# MCU152A_F28E12X_Device.net
KiCad netlist of a schematic drawn in Altium Designer
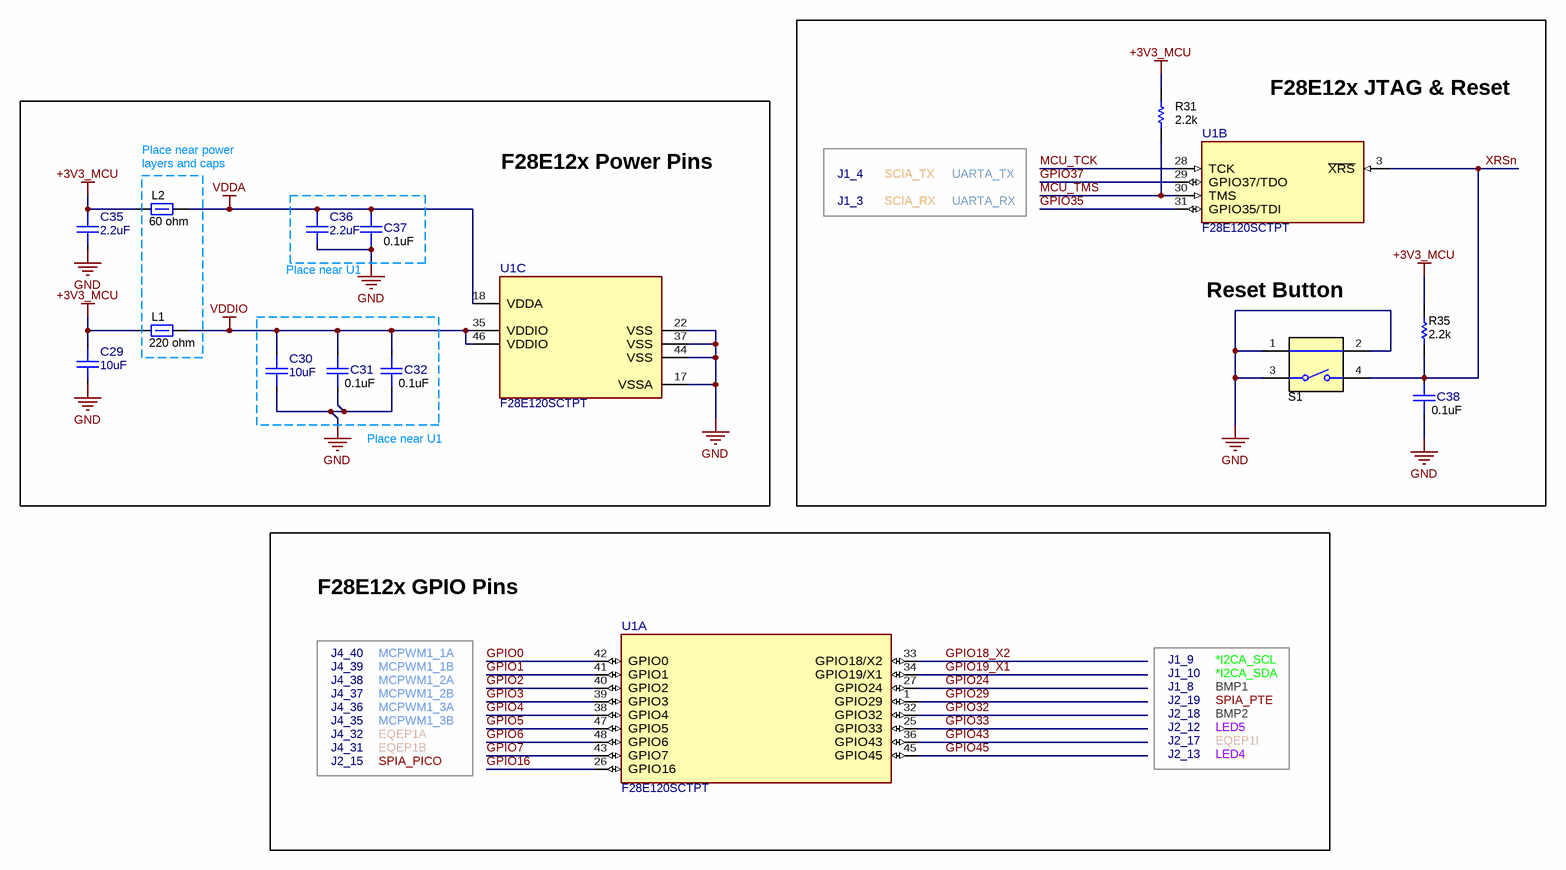
[diagram p0: MCU152A_F28E12X_Device.SchDoc]

(export (version "E")
  (design (tool "Eeschema 10.0.6"))
  (components
    (comp (ref "C29")
      (value "885012106031")
      (footprint "FP-885012106031_0603-MFG")
      (description "10 µF ±20% 25V Ceramic Capacitor X5R 0603 (1608 Metric)")
      (fields (field (name "MANUFACTURER") "Wurth") (field (name "VALUEDISPLAYED") "10uF"))
      (libsource (lib "Altium Vault - TI") (part "SYM-885012106031"))
    )
    (comp (ref "C30")
      (value "885012106031")
      (footprint "FP-885012106031_0603-MFG")
      (description "10 µF ±20% 25V Ceramic Capacitor X5R 0603 (1608 Metric)")
      (fields (field (name "MANUFACTURER") "Wurth") (field (name "VALUEDISPLAYED") "10uF"))
      (libsource (lib "Altium Vault - TI") (part "SYM-885012106031"))
    )
    (comp (ref "C31")
      (value "885012205018")
      (footprint "FP-885012205018_0402-MFG")
      (description "0.1µF ±10% 10V Ceramic Capacitor X7R 0402 (1005 Metric)")
      (fields
        (field (name "MANUFACTURER") "Wurth Electronics")
        (field (name "MOUSER PART NUMBER") "710-885012205018")
        (field (name "VALUEDISPLAYED") "0.1uF")
      )
      (libsource (lib "Altium Vault - TI") (part "SYM-885012205018"))
    )
    (comp (ref "C32")
      (value "885012205018")
      (footprint "FP-885012205018_0402-MFG")
      (description "0.1µF ±10% 10V Ceramic Capacitor X7R 0402 (1005 Metric)")
      (fields
        (field (name "MANUFACTURER") "Wurth Electronics")
        (field (name "MOUSER PART NUMBER") "710-885012205018")
        (field (name "VALUEDISPLAYED") "0.1uF")
      )
      (libsource (lib "Altium Vault - TI") (part "SYM-885012205018"))
    )
    (comp (ref "C35")
      (value "885012106011")
      (footprint "FP-885012106011_0603-MFG")
      (description "2.2 µF ±20% 10V Ceramic Capacitor X5R 0603 (1608 Metric)")
      (fields
        (field (name "MANUFACTURER") "Wurth Electronics")
        (field (name "VALUEDISPLAYED") "2.2uF")
        (field (name "DIGIKEY PART NUMBER") "732-7908-1-ND")
      )
      (libsource (lib "Altium Vault - TI") (part "SYM-885012106011"))
    )
    (comp (ref "C36")
      (value "885012106011")
      (footprint "FP-885012106011_0603-MFG")
      (description "2.2 µF ±20% 10V Ceramic Capacitor X5R 0603 (1608 Metric)")
      (fields
        (field (name "MANUFACTURER") "Wurth Electronics")
        (field (name "VALUEDISPLAYED") "2.2uF")
        (field (name "DIGIKEY PART NUMBER") "732-7908-1-ND")
      )
      (libsource (lib "Altium Vault - TI") (part "SYM-885012106011"))
    )
    (comp (ref "C37")
      (value "885012205018")
      (footprint "FP-885012205018_0402-MFG")
      (description "0.1µF ±10% 10V Ceramic Capacitor X7R 0402 (1005 Metric)")
      (fields
        (field (name "MANUFACTURER") "Wurth Electronics")
        (field (name "MOUSER PART NUMBER") "710-885012205018")
        (field (name "VALUEDISPLAYED") "0.1uF")
      )
      (libsource (lib "Altium Vault - TI") (part "SYM-885012205018"))
    )
    (comp (ref "C38")
      (value "885012205018")
      (footprint "FP-885012205018_0402-MFG")
      (description "0.1µF ±10% 10V Ceramic Capacitor X7R 0402 (1005 Metric)")
      (fields
        (field (name "MANUFACTURER") "Wurth Electronics")
        (field (name "MOUSER PART NUMBER") "710-885012205018")
        (field (name "VALUEDISPLAYED") "0.1uF")
      )
      (libsource (lib "Altium Vault - TI") (part "SYM-885012205018"))
    )
    (comp (ref "L1")
      (value "742792022")
      (footprint "0805_HV")
      (description "Ferrite Bead, 220 ohm @ 100 MHz, 2 A, 0805")
      (fields
        (field (name "MANUFACTURER") "Wurth Elektronik")
        (field (name "VALUEDISPLAYED") "220 ohm")
        (field (name "PUBLISHER") "Texas Instruments")
      )
      (libsource (lib "Altium Vault - TI") (part "Ferrite_Bead"))
    )
    (comp (ref "L2")
      (value "60 ohm")
      (footprint "0805_HV")
      (description "Ferrite Bead, 60 ohm @ 100 MHz, 3 A, 0805")
      (fields
        (field (name "MANUFACTURER") "Wurth Elektronik")
        (field (name "PARTNUMBER") "742792063")
        (field (name "PUBLISHER") "Texas Instruments")
      )
      (libsource (lib "Altium Vault - TI") (part "Ferrite_Bead"))
    )
    (comp (ref "R31")
      (value "CRCW04022K20JNED")
      (footprint "0402")
      (description "RES, 2.2 k, 5%, 0.063 W, AEC-Q200 Grade 0, 0402")
      (fields (field (name "VALUEDISPLAYED") "2.2k") (field (name "MANUFACTURER") "Vishay-Dale"))
      (libsource (lib "Altium Vault - TI") (part "Resistor"))
    )
    (comp (ref "R35")
      (value "CRCW04022K20JNED")
      (footprint "0402")
      (description "RES, 2.2 k, 5%, 0.063 W, AEC-Q200 Grade 0, 0402")
      (fields (field (name "VALUEDISPLAYED") "2.2k") (field (name "MANUFACTURER") "Vishay-Dale"))
      (libsource (lib "Altium Vault - TI") (part "Resistor"))
    )
    (comp (ref "S1")
      (value "1188E-1K2-V-TR")
      (footprint "SW_1188E")
      (description "Switch, SPST, 0.05 A, 12 VDC, SMD")
      (fields (field (name "MANUFACTURER") "Diptronics") (field (name "PUBLISHER") "Texas Instruments"))
      (libsource (lib "Altium Vault - TI") (part "SW_1188E"))
    )
    (comp (ref "U1")
      (value "F28E120SCTPT")
      (footprint "PT0048A-MFG")
      (description "F28E12x Real-Time Microcontrollers")
      (fields (field (name "MANUFACTURER") "Texas Instruments") (field (name "PARTNUMBER") "F28E120SCTPT"))
      (libsource (lib "Altium Vault - TI") (part "SYM-F28E120SCTPT"))
    )
  )
  (nets
    (net (code "1") (name "+3V3_MCU") (class "Default")
      (node (ref "C29") (pin "1") (pinfunction "1_1") (pintype "passive"))
      (node (ref "C35") (pin "1") (pinfunction "1_1") (pintype "passive"))
      (node (ref "L1") (pin "1") (pinfunction "1_1") (pintype "passive"))
      (node (ref "L2") (pin "1") (pinfunction "1_1") (pintype "passive"))
      (node (ref "R31") (pin "2") (pinfunction "2_2") (pintype "passive"))
      (node (ref "R35") (pin "2") (pinfunction "2_2") (pintype "passive"))
    )
    (net (code "2") (name "/GPIO0") (class "Default")
      (node (ref "U1") (pin "42") (pinfunction "GPIO0_42") (pintype "bidirectional"))
    )
    (net (code "3") (name "/GPIO1") (class "Default")
      (node (ref "U1") (pin "41") (pinfunction "GPIO1_41") (pintype "bidirectional"))
    )
    (net (code "4") (name "/GPIO2") (class "Default")
      (node (ref "U1") (pin "40") (pinfunction "GPIO2_40") (pintype "bidirectional"))
    )
    (net (code "5") (name "/GPIO3") (class "Default")
      (node (ref "U1") (pin "39") (pinfunction "GPIO3_39") (pintype "bidirectional"))
    )
    (net (code "6") (name "/GPIO4") (class "Default")
      (node (ref "U1") (pin "38") (pinfunction "GPIO4_38") (pintype "bidirectional"))
    )
    (net (code "7") (name "/GPIO5") (class "Default")
      (node (ref "U1") (pin "47") (pinfunction "GPIO5_47") (pintype "bidirectional"))
    )
    (net (code "8") (name "/GPIO6") (class "Default")
      (node (ref "U1") (pin "48") (pinfunction "GPIO6_48") (pintype "bidirectional"))
    )
    (net (code "9") (name "/GPIO7") (class "Default")
      (node (ref "U1") (pin "43") (pinfunction "GPIO7_43") (pintype "bidirectional"))
    )
    (net (code "10") (name "/GPIO16") (class "Default")
      (node (ref "U1") (pin "26") (pinfunction "GPIO16_26") (pintype "bidirectional"))
    )
    (net (code "11") (name "/GPIO18_X2") (class "Default")
      (node (ref "U1") (pin "33") (pinfunction "GPIO18/X2_33") (pintype "bidirectional"))
    )
    (net (code "12") (name "/GPIO19_X1") (class "Default")
      (node (ref "U1") (pin "34") (pinfunction "GPIO19/X1_34") (pintype "bidirectional"))
    )
    (net (code "13") (name "/GPIO24") (class "Default")
      (node (ref "U1") (pin "27") (pinfunction "GPIO24_27") (pintype "bidirectional"))
    )
    (net (code "14") (name "/GPIO29") (class "Default")
      (node (ref "U1") (pin "1") (pinfunction "GPIO29_1") (pintype "bidirectional"))
    )
    (net (code "15") (name "/GPIO32") (class "Default")
      (node (ref "U1") (pin "32") (pinfunction "GPIO32_32") (pintype "bidirectional"))
    )
    (net (code "16") (name "/GPIO33") (class "Default")
      (node (ref "U1") (pin "25") (pinfunction "GPIO33_25") (pintype "bidirectional"))
    )
    (net (code "17") (name "/GPIO35") (class "Default")
      (node (ref "U1") (pin "31") (pinfunction "GPIO35/TDI_31") (pintype "bidirectional"))
    )
    (net (code "18") (name "/GPIO37") (class "Default")
      (node (ref "U1") (pin "29") (pinfunction "GPIO37/TDO_29") (pintype "bidirectional"))
    )
    (net (code "19") (name "/GPIO43") (class "Default")
      (node (ref "U1") (pin "36") (pinfunction "GPIO43_36") (pintype "bidirectional"))
    )
    (net (code "20") (name "/GPIO45") (class "Default")
      (node (ref "U1") (pin "45") (pinfunction "GPIO45_45") (pintype "bidirectional"))
    )
    (net (code "21") (name "/MCU_TCK") (class "Default")
      (node (ref "U1") (pin "28") (pinfunction "TCK_28") (pintype "input"))
    )
    (net (code "22") (name "/MCU_TMS") (class "Default")
      (node (ref "R31") (pin "1") (pinfunction "1_1") (pintype "passive"))
      (node (ref "U1") (pin "30") (pinfunction "TMS_30") (pintype "input"))
    )
    (net (code "23") (name "/XRSn") (class "Default")
      (node (ref "C38") (pin "2") (pinfunction "2_2") (pintype "passive"))
      (node (ref "R35") (pin "1") (pinfunction "1_1") (pintype "passive"))
      (node (ref "S1") (pin "4") (pinfunction "4_4") (pintype "passive"))
      (node (ref "U1") (pin "3") (pinfunction "~{XRS}_3") (pintype "input"))
    )
    (net (code "24") (name "GND") (class "Default")
      (node (ref "C29") (pin "2") (pinfunction "2_2") (pintype "passive"))
      (node (ref "C30") (pin "2") (pinfunction "2_2") (pintype "passive"))
      (node (ref "C31") (pin "1") (pinfunction "1_1") (pintype "passive"))
      (node (ref "C32") (pin "1") (pinfunction "1_1") (pintype "passive"))
      (node (ref "C35") (pin "2") (pinfunction "2_2") (pintype "passive"))
      (node (ref "C36") (pin "2") (pinfunction "2_2") (pintype "passive"))
      (node (ref "C37") (pin "1") (pinfunction "1_1") (pintype "passive"))
      (node (ref "C38") (pin "1") (pinfunction "1_1") (pintype "passive"))
      (node (ref "S1") (pin "1") (pinfunction "1_1") (pintype "passive"))
      (node (ref "S1") (pin "2") (pinfunction "2_2") (pintype "passive"))
      (node (ref "S1") (pin "3") (pinfunction "3_3") (pintype "passive"))
      (node (ref "U1") (pin "17") (pinfunction "VSSA_17") (pintype "power_in"))
      (node (ref "U1") (pin "22") (pinfunction "VSS_22") (pintype "power_in"))
      (node (ref "U1") (pin "37") (pinfunction "VSS_37") (pintype "power_in"))
      (node (ref "U1") (pin "44") (pinfunction "VSS_44") (pintype "power_in"))
    )
    (net (code "25") (name "VDDA") (class "Default")
      (node (ref "C36") (pin "1") (pinfunction "1_1") (pintype "passive"))
      (node (ref "C37") (pin "2") (pinfunction "2_2") (pintype "passive"))
      (node (ref "L2") (pin "2") (pinfunction "2_2") (pintype "passive"))
      (node (ref "U1") (pin "18") (pinfunction "VDDA_18") (pintype "power_in"))
    )
    (net (code "26") (name "VDDIO") (class "Default")
      (node (ref "C30") (pin "1") (pinfunction "1_1") (pintype "passive"))
      (node (ref "C31") (pin "2") (pinfunction "2_2") (pintype "passive"))
      (node (ref "C32") (pin "2") (pinfunction "2_2") (pintype "passive"))
      (node (ref "L1") (pin "2") (pinfunction "2_2") (pintype "passive"))
      (node (ref "U1") (pin "35") (pinfunction "VDDIO_35") (pintype "power_in"))
      (node (ref "U1") (pin "46") (pinfunction "VDDIO_46") (pintype "power_in"))
    )
  )
)
